# Power.net
KiCad netlist of a schematic drawn in Altium Designer
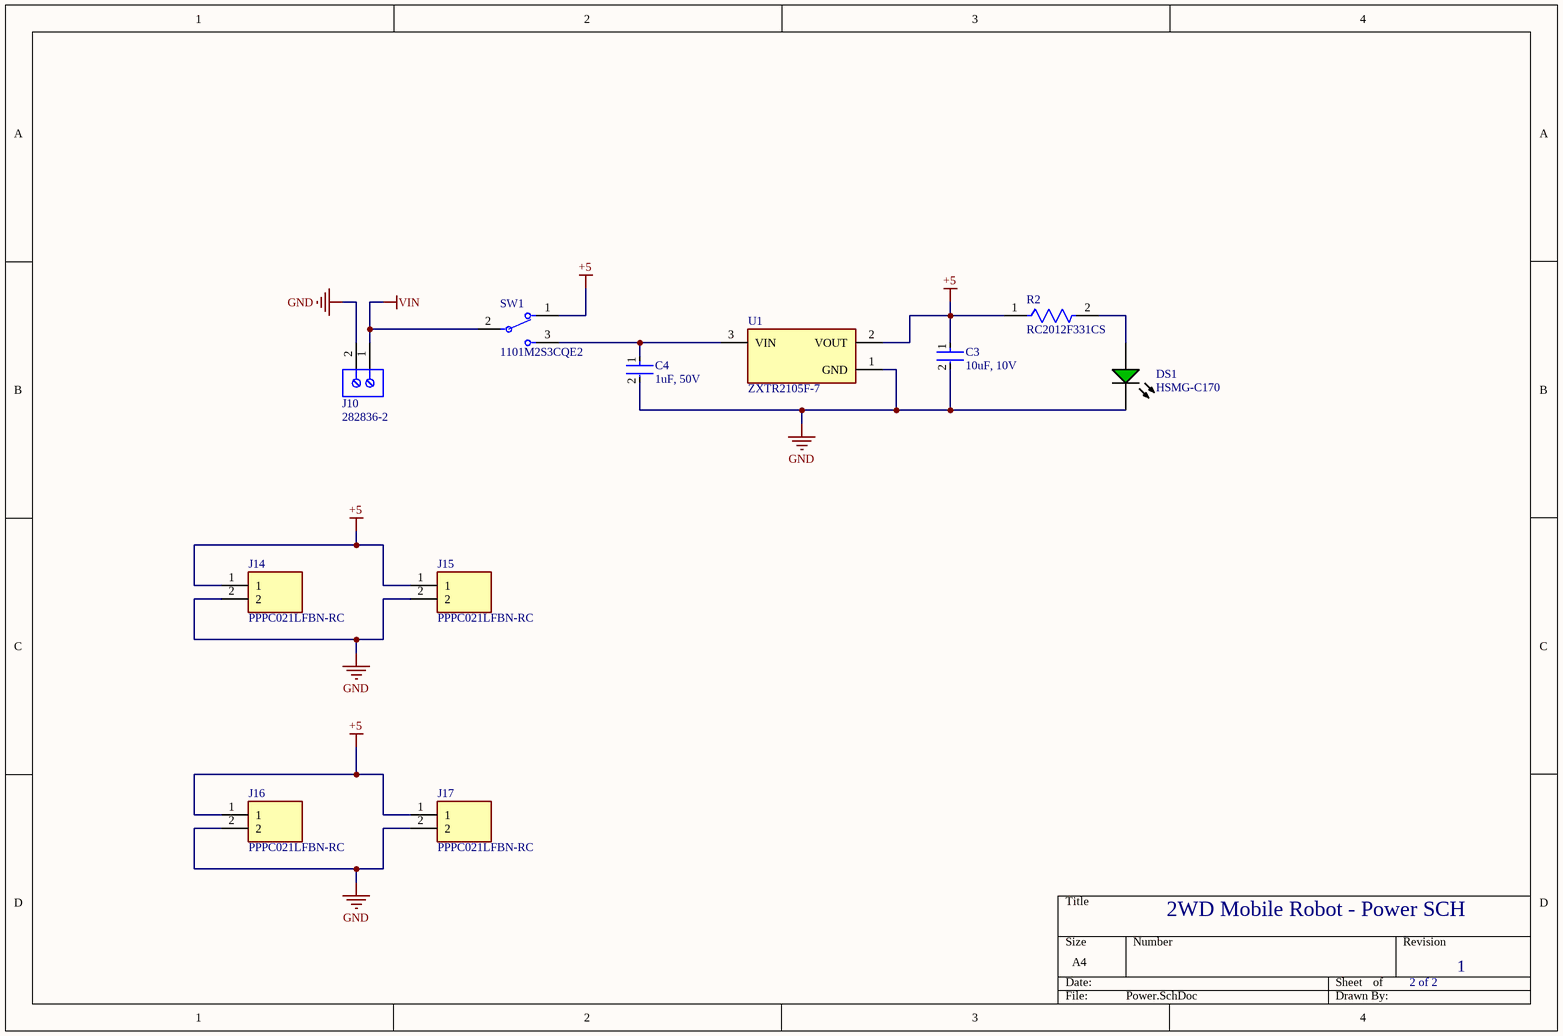
[diagram p0: Power.SchDoc]

(export (version "E")
  (design (tool "Eeschema 10.0.6"))
  (components
    (comp (ref "C3")
      (value "10uF, 10V")
      (footprint "FP-C0805C-DG-MFG")
      (description "CAP CER 10UF 10V X5R 0805")
      (fields (field (name "TOLERANCE") "10%") (field (name "MANUFACTURER PART NUMBER") "C0805C106K8PACTU"))
      (libsource (lib "Altium Content Vault") (part "11868f565c42a9108669ba33697ecf6"))
    )
    (comp (ref "C4")
      (value "1uF, 50V")
      (footprint "FP-C2012-125-0_2-IPC_A")
      (description "Multilayer Ceramic Capacitors 1μF ±10% 50V JB SMD 0805")
      (fields (field (name "TOLERANCE") "10%"))
      (libsource (lib "Altium Content Vault") (part "b4654b650e69147ec39a6b967a45e02"))
    )
    (comp (ref "DS1")
      (value "HSMG-C170")
      (footprint "AVAG-HSMX-C170_V")
      (description "Chip LED, Green, 2.2 V, -40 to 85 degC, 2-Pin SMD, Pb-Free, Tape and Reel")
      (fields (field (name "MANUFACTURER") "Avago"))
      (libsource (lib "Altium Content Vault") (part "LED_GREEN_A1K2-2"))
    )
    (comp (ref "J10")
      (value "282836-2")
      (footprint "TECO-282836-2_V")
      (description "Female Header, Pitch 5 mm, 1 x 2 Position, Height 10 mm, Tail Length 3.5 mm, Rohs, Bulk")
      (fields (field (name "VOLTAGE") "300V") (field (name "MANUFACTURER") "TE Connectivity"))
      (libsource (lib "Altium Content Vault") (part "CN-1P-F-TB2"))
    )
    (comp (ref "J14")
      (value "PPPC021LFBN-RC")
      (footprint "SamacSys:RHDR2W80P0X254_1X2_558X254X850P")
      (description "Connector")
      (libsource (lib "*") (part "PPPC021LFBN-RC"))
    )
    (comp (ref "J15")
      (value "PPPC021LFBN-RC")
      (footprint "SamacSys:RHDR2W80P0X254_1X2_558X254X850P")
      (description "Connector")
      (libsource (lib "*") (part "PPPC021LFBN-RC"))
    )
    (comp (ref "J16")
      (value "PPPC021LFBN-RC")
      (footprint "SamacSys:RHDR2W80P0X254_1X2_558X254X850P")
      (description "Connector")
      (libsource (lib "*") (part "PPPC021LFBN-RC"))
    )
    (comp (ref "J17")
      (value "PPPC021LFBN-RC")
      (footprint "SamacSys:RHDR2W80P0X254_1X2_558X254X850P")
      (description "Connector")
      (libsource (lib "*") (part "PPPC021LFBN-RC"))
    )
    (comp (ref "R2")
      (value "RC2012F331CS")
      (footprint "FP-RC2012-MFG")
      (description "Res Thick Film 0805 330Ω 1% 0.125W ±100ppm/°C Molded SMD T/R")
      (fields (field (name "TOLERANCE") "1%"))
      (libsource (lib "Altium Content Vault") (part "1029c3af85768c4190bb7ad29bc67b5"))
    )
    (comp (ref "SW1")
      (value "1101M2S3CQE2")
      (footprint "FP-1101M2S3CQE2-MFG")
      (description "SWITCH SLIDE SPDT 6A 120V")
      (libsource (lib "Altium Content Vault") (part "7fcaa069a19c2acd609832313418d7c"))
    )
    (comp (ref "U1")
      (value "ZXTR2105F-7")
      (footprint "FP-SOT23-MFG")
      (description "IC REG LINEAR 5V 89MA SOT23")
      (libsource (lib "Altium Content Vault") (part "1945c84baa43fbed35894b2e56c3732"))
    )
  )
  (nets
    (net (code "1") (name "+5") (class "Default")
      (node (ref "C3") (pin "1") (pinfunction "1_1") (pintype "passive"))
      (node (ref "J14") (pin "1") (pinfunction "1_1") (pintype "passive"))
      (node (ref "J15") (pin "1") (pinfunction "1_1") (pintype "passive"))
      (node (ref "J16") (pin "1") (pinfunction "1_1") (pintype "passive"))
      (node (ref "J17") (pin "1") (pinfunction "1_1") (pintype "passive"))
      (node (ref "R2") (pin "1") (pinfunction "1_1") (pintype "passive"))
      (node (ref "SW1") (pin "1") (pinfunction "1_1") (pintype "passive"))
      (node (ref "U1") (pin "2") (pinfunction "VOUT_2") (pintype "power_in"))
    )
    (net (code "2") (name "GND") (class "Default")
      (node (ref "C3") (pin "2") (pinfunction "2_2") (pintype "passive"))
      (node (ref "C4") (pin "2") (pinfunction "2_2") (pintype "passive"))
      (node (ref "DS1") (pin "2") (pinfunction "K_2") (pintype "passive"))
      (node (ref "J10") (pin "2") (pinfunction "2_2") (pintype "passive"))
      (node (ref "J14") (pin "2") (pinfunction "2_2") (pintype "passive"))
      (node (ref "J15") (pin "2") (pinfunction "2_2") (pintype "passive"))
      (node (ref "J16") (pin "2") (pinfunction "2_2") (pintype "passive"))
      (node (ref "J17") (pin "2") (pinfunction "2_2") (pintype "passive"))
      (node (ref "U1") (pin "1") (pinfunction "GND_1") (pintype "power_in"))
    )
    (net (code "3") (name "Net-(DS1-A)") (class "Default")
      (node (ref "DS1") (pin "1") (pinfunction "A_1") (pintype "passive"))
      (node (ref "R2") (pin "2") (pinfunction "2_2") (pintype "passive"))
    )
    (net (code "4") (name "Net-(U1-VIN)") (class "Default")
      (node (ref "C4") (pin "1") (pinfunction "1_1") (pintype "passive"))
      (node (ref "SW1") (pin "3") (pinfunction "3_3") (pintype "passive"))
      (node (ref "U1") (pin "3") (pinfunction "VIN_3") (pintype "power_in"))
    )
    (net (code "5") (name "VIN") (class "Default")
      (node (ref "J10") (pin "1") (pinfunction "1_1") (pintype "passive"))
      (node (ref "SW1") (pin "2") (pinfunction "COMM_2") (pintype "passive"))
    )
  )
)
